# design.net
KiCad netlist of a schematic drawn in Altium Designer
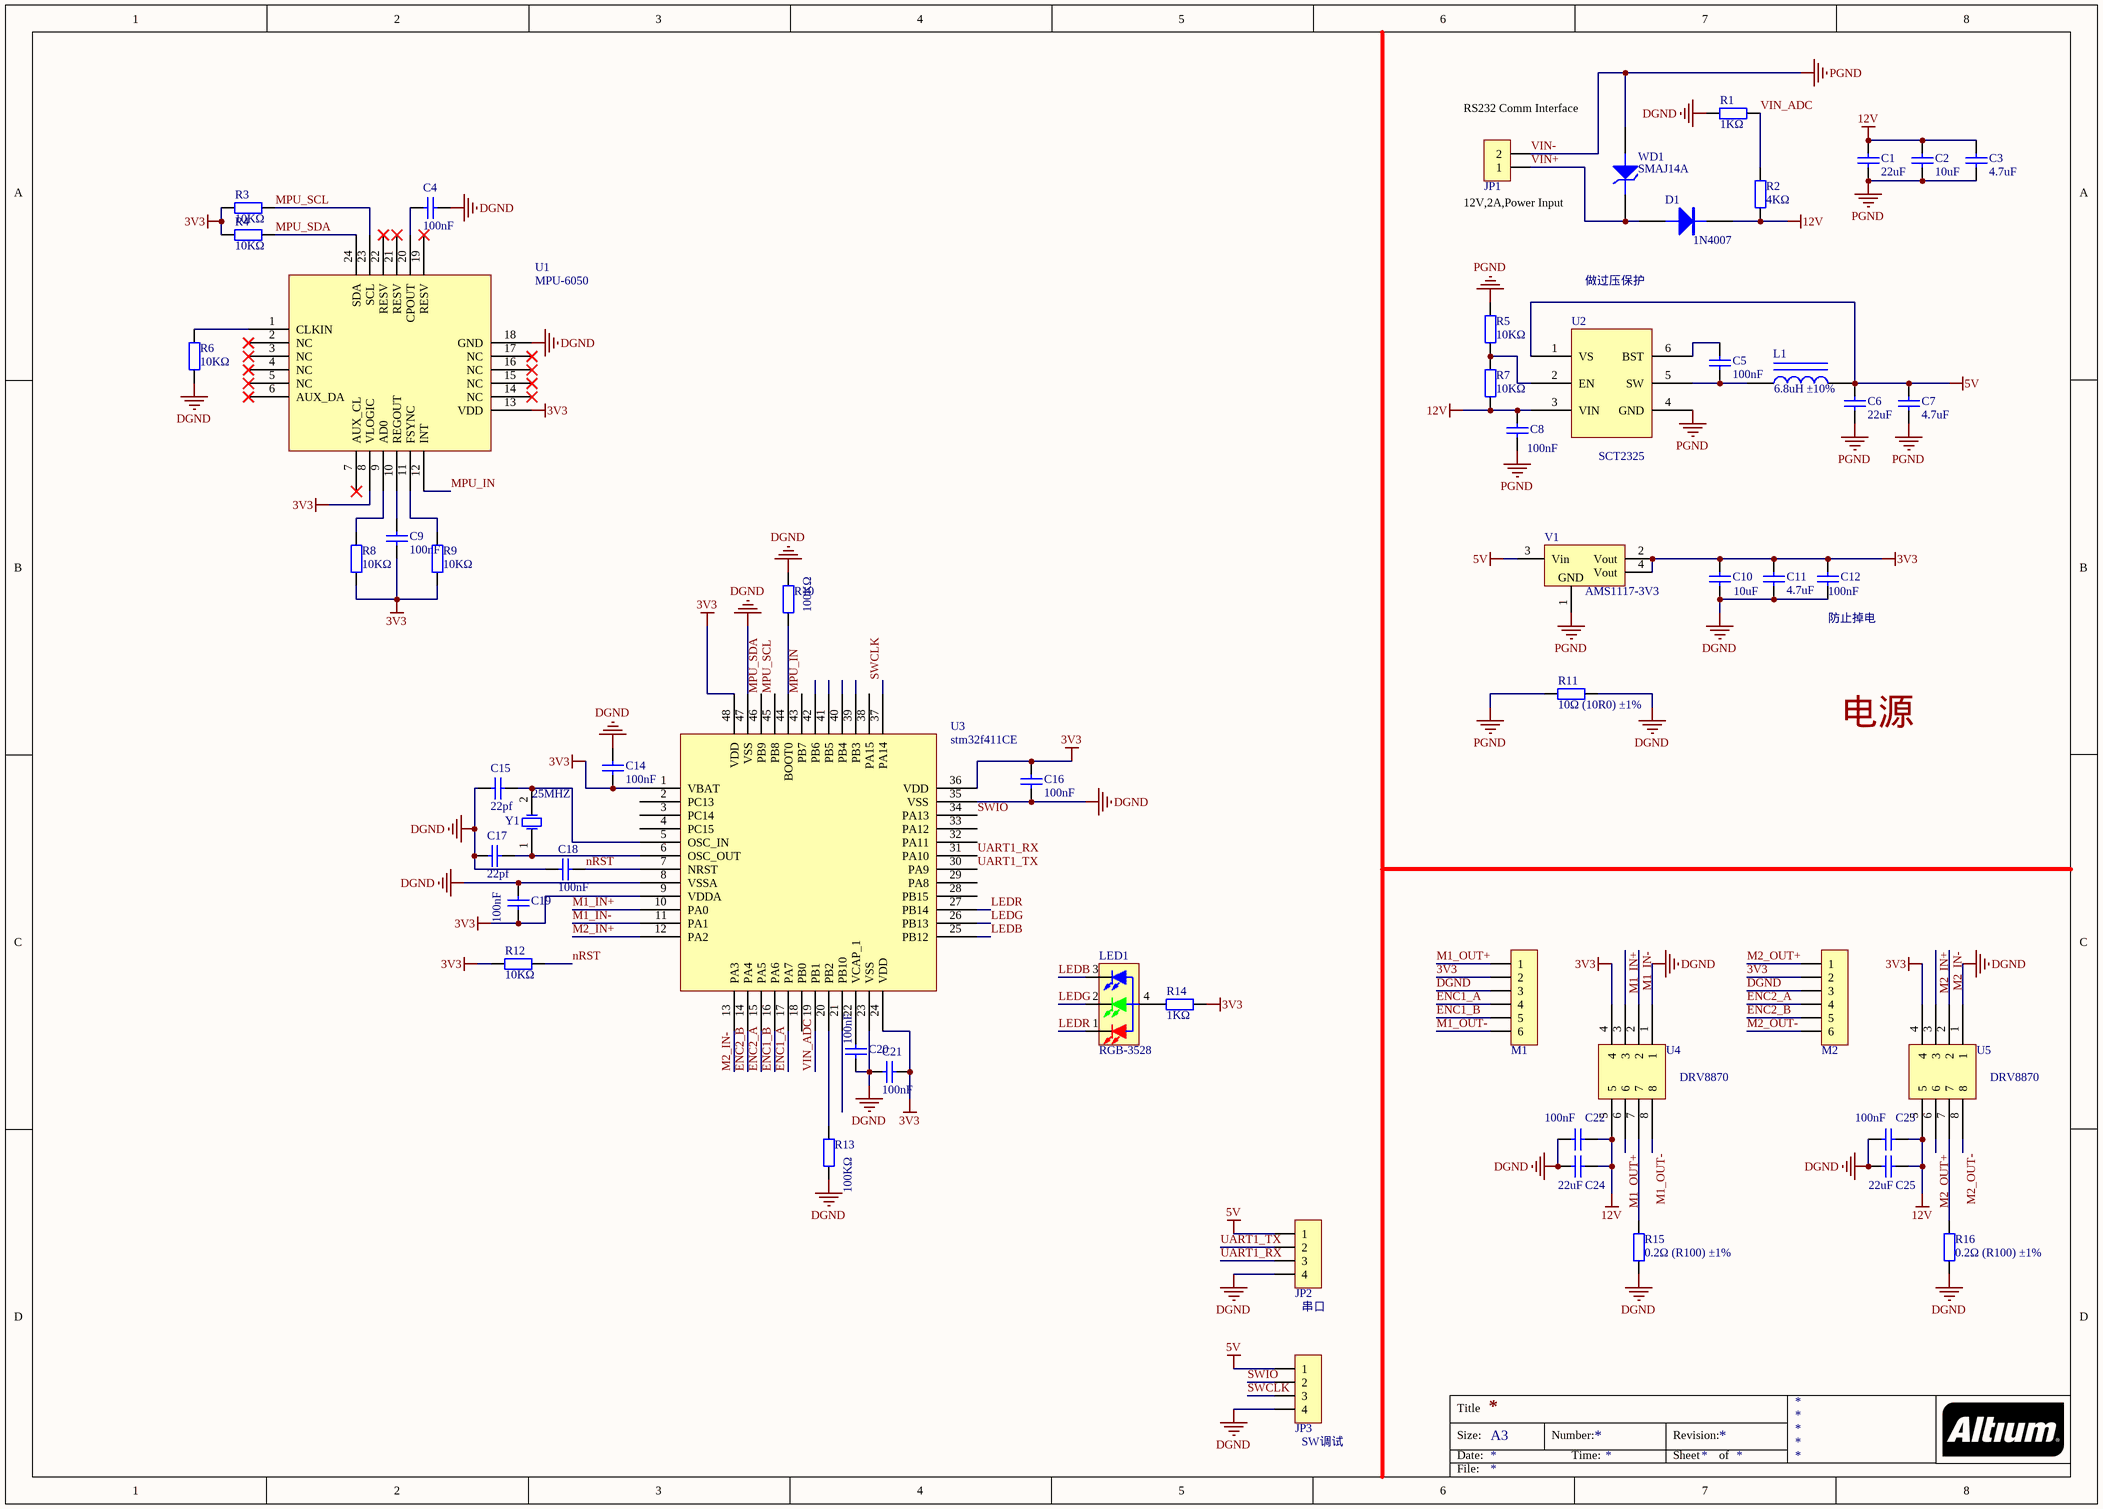
[diagram p0: 驱动控制板原理图.SchDoc]

(export (version "E")
  (design (tool "Eeschema 10.0.6"))
  (components
    (comp (ref "C1")
      (value "22uF")
      (footprint "LC-1206_C")
      (description "CAP TAN 22uF 20V T-Case B")
      (fields (field (name "PUBLISHER") "Altium Limited"))
      (libsource (lib "*") (part "Cap Semi"))
    )
    (comp (ref "C2")
      (value "10uF")
      (footprint "LC-0805_C")
      (description "CAP TAN 22uF 20V T-Case B")
      (fields (field (name "PUBLISHER") "Altium Limited"))
      (libsource (lib "*") (part "Cap Semi"))
    )
    (comp (ref "C3")
      (value "4.7uF")
      (footprint "LC-0603_C")
      (description "CAP TAN 22uF 20V T-Case B")
      (fields (field (name "PUBLISHER") "Altium Limited"))
      (libsource (lib "*") (part "Cap Semi"))
    )
    (comp (ref "C4")
      (value "100nF")
      (footprint "LC-0402_C")
      (description "CAP ceramic  0.1uF  X7R, SMD 0603")
      (fields
        (field (name "MANUFACTURER") "Generic Components")
        (field (name "PUBLISHER") "Altium Hobart Technology Centre")
      )
      (libsource (lib "*") (part "Cap"))
    )
    (comp (ref "C5")
      (value "100nF")
      (footprint "LC-0402_C")
      (description "贴片电容")
      (libsource (lib "立创封装库") (part "0603 100nF (104) 10% 50V"))
    )
    (comp (ref "C6")
      (value "22uF")
      (footprint "LC-1206_C")
      (description "贴片电容")
      (libsource (lib "立创封装库") (part "0805 22uF (226) 20% 25V"))
    )
    (comp (ref "C7")
      (value "4.7uF")
      (footprint "LC-0603_C")
      (description "CAP TAN 22uF 20V T-Case B")
      (fields (field (name "PUBLISHER") "Altium Limited"))
      (libsource (lib "*") (part "Cap Semi"))
    )
    (comp (ref "C8")
      (value "100nF")
      (footprint "LC-0402_C")
      (description "CAP ceramic  0.1uF  X7R, SMD 0603")
      (fields
        (field (name "MANUFACTURER") "Generic Components")
        (field (name "PUBLISHER") "Altium Hobart Technology Centre")
      )
      (libsource (lib "*") (part "Cap"))
    )
    (comp (ref "C9")
      (value "100nF")
      (footprint "LC-0402_C")
      (description "CAP ceramic  0.1uF  X7R, SMD 0603")
      (fields
        (field (name "MANUFACTURER") "Generic Components")
        (field (name "PUBLISHER") "Altium Hobart Technology Centre")
      )
      (libsource (lib "*") (part "Cap"))
    )
    (comp (ref "C10")
      (value "10uF")
      (footprint "LC-0805_C")
      (description "CAP TAN 22uF 20V T-Case B")
      (fields (field (name "PUBLISHER") "Altium Limited"))
      (libsource (lib "*") (part "Cap Semi"))
    )
    (comp (ref "C11")
      (value "4.7uF")
      (footprint "LC-0603_C")
      (description "CAP TAN 22uF 20V T-Case B")
      (fields (field (name "PUBLISHER") "Altium Limited"))
      (libsource (lib "*") (part "Cap Semi"))
    )
    (comp (ref "C12")
      (value "100nF")
      (footprint "LC-0402_C")
      (description "贴片电容")
      (libsource (lib "立创封装库") (part "0402 100nF (104) 10% 16V"))
    )
    (comp (ref "C14")
      (value "100nF")
      (footprint "LC-0402_C")
      (description "贴片电容")
      (libsource (lib "立创封装库") (part "0603 100nF (104) 10% 50V"))
    )
    (comp (ref "C15")
      (value "22pf")
      (footprint "LC-0402_C")
      (description "贴片电容")
      (libsource (lib "立创封装库") (part "0603 100nF (104) 10% 50V"))
    )
    (comp (ref "C16")
      (value "100nF")
      (footprint "LC-0402_C")
      (description "贴片电容")
      (libsource (lib "立创封装库") (part "0603 100nF (104) 10% 50V"))
    )
    (comp (ref "C17")
      (value "22pf")
      (footprint "LC-0402_C")
      (description "贴片电容")
      (libsource (lib "立创封装库") (part "0603 100nF (104) 10% 50V"))
    )
    (comp (ref "C18")
      (value "100nF")
      (footprint "LC-0402_C")
      (description "贴片电容")
      (libsource (lib "立创封装库") (part "0603 100nF (104) 10% 50V"))
    )
    (comp (ref "C19")
      (value "100nF")
      (footprint "LC-0402_C")
      (description "贴片电容")
      (libsource (lib "立创封装库") (part "0603 100nF (104) 10% 50V"))
    )
    (comp (ref "C20")
      (value "100nF")
      (footprint "LC-0402_C")
      (description "贴片电容")
      (libsource (lib "立创封装库") (part "0603 100nF (104) 10% 50V"))
    )
    (comp (ref "C21")
      (value "100nF")
      (footprint "LC-0402_C")
      (description "贴片电容")
      (libsource (lib "立创封装库") (part "0603 100nF (104) 10% 50V"))
    )
    (comp (ref "C22")
      (value "100nF")
      (footprint "LC-0805_C")
      (description "贴片电容")
      (libsource (lib "立创封装库") (part "0603 100nF (104) 10% 50V"))
    )
    (comp (ref "C23")
      (value "100nF")
      (footprint "LC-0805_C")
      (description "贴片电容")
      (libsource (lib "立创封装库") (part "0603 100nF (104) 10% 50V"))
    )
    (comp (ref "C24")
      (value "22uF")
      (footprint "LC-1206_C")
      (description "贴片电容")
      (libsource (lib "立创封装库") (part "0805 22uF (226) 20% 25V"))
    )
    (comp (ref "C25")
      (value "22uF")
      (footprint "LC-1206_C")
      (description "贴片电容")
      (libsource (lib "立创封装库") (part "0805 22uF (226) 20% 25V"))
    )
    (comp (ref "D1")
      (value "1N4007")
      (footprint "SMA")
      (description "Diode")
      (libsource (lib "*") (part "DIODE"))
    )
    (comp (ref "JP1")
      (value "HDR-1X2")
      (footprint "PH2.0-WI-2P")
      (description "2P接插件")
      (libsource (lib "5.3 - 接插件-脚距2.0") (part "Header 2"))
    )
    (comp (ref "JP2")
      (value "串口")
      (footprint "MX 1.25-WI-4P")
      (description "4P接插件")
      (libsource (lib "5.0 - 接插件-脚距1.25") (part "Header 4"))
    )
    (comp (ref "JP3")
      (value "SW调试")
      (footprint "MX 1.25-WI-4P")
      (description "4P接插件")
      (libsource (lib "5.0 - 接插件-脚距1.25") (part "Header 4"))
    )
    (comp (ref "L1")
      (value "6.8uH ±10%")
      (footprint "L-SMD-0630")
      (description "贴片电感")
      (libsource (lib "立创封装库") (part "1206 10uH 10%"))
    )
    (comp (ref "LED1")
      (value "RGB-3528")
      (footprint "LED 3528-4Pin")
      (description "3528三基色LED")
      (libsource (lib "0.3 - LED发光二极管") (part "LED-RGB 3528"))
    )
    (comp (ref "M1")
      (value "HDR-1X6")
      (footprint "ZH1.5-WI-6P")
      (description "6P接插件")
      (libsource (lib "5.2 - 接插件-脚距1.5") (part "Header 6"))
    )
    (comp (ref "M2")
      (value "HDR-1X6")
      (footprint "ZH1.5-WI-6P")
      (description "6P接插件")
      (libsource (lib "5.2 - 接插件-脚距1.5") (part "Header 6"))
    )
    (comp (ref "R1")
      (value "1KΩ")
      (footprint "LC-0402_R")
      (description "贴片电阻")
      (libsource (lib "") (part "0402 10KΩ (1002) 1%_1"))
    )
    (comp (ref "R2")
      (value "4KΩ")
      (footprint "LC-0402_R")
      (description "贴片电阻")
      (libsource (lib "立创封装库") (part "0402 10KΩ (1002) 1%"))
    )
    (comp (ref "R3")
      (value "10KΩ")
      (footprint "LC-0402_R")
      (description "贴片电阻")
      (libsource (lib "") (part "0402 10KΩ (1002) 1%_1"))
    )
    (comp (ref "R4")
      (value "10KΩ")
      (footprint "LC-0402_R")
      (description "贴片电阻")
      (libsource (lib "") (part "0402 10KΩ (1002) 1%_1"))
    )
    (comp (ref "R5")
      (value "10KΩ")
      (footprint "LC-0402_R")
      (description "贴片电阻")
      (libsource (lib "立创封装库") (part "0402 10KΩ (1002) 1%"))
    )
    (comp (ref "R6")
      (value "10KΩ")
      (footprint "LC-0402_R")
      (description "贴片电阻")
      (libsource (lib "立创封装库") (part "0402 10KΩ (1002) 1%"))
    )
    (comp (ref "R7")
      (value "10KΩ")
      (footprint "LC-0402_R")
      (description "贴片电阻")
      (libsource (lib "立创封装库") (part "0402 10KΩ (1002) 1%"))
    )
    (comp (ref "R8")
      (value "10KΩ")
      (footprint "LC-0402_R")
      (description "贴片电阻")
      (libsource (lib "立创封装库") (part "0402 10KΩ (1002) 1%"))
    )
    (comp (ref "R9")
      (value "10KΩ")
      (footprint "LC-0402_R")
      (description "贴片电阻")
      (libsource (lib "立创封装库") (part "0402 10KΩ (1002) 1%"))
    )
    (comp (ref "R10")
      (value "100KΩ")
      (footprint "LC-0402_R")
      (description "贴片电阻")
      (libsource (lib "立创封装库") (part "0603 110KΩ (1103) 1%"))
    )
    (comp (ref "R11")
      (value "10Ω (10R0) ±1%")
      (footprint "LC-1206_R")
      (description "贴片电阻")
      (libsource (lib "立创封装库") (part "1206 10Ω (10R0) 1%"))
    )
    (comp (ref "R12")
      (value "10KΩ")
      (footprint "LC-0402_R")
      (description "贴片电阻")
      (libsource (lib "") (part "0603 110KΩ (1103) 1%_1"))
    )
    (comp (ref "R13")
      (value "100KΩ")
      (footprint "LC-0402_R")
      (description "贴片电阻")
      (libsource (lib "立创封装库") (part "0603 110KΩ (1103) 1%"))
    )
    (comp (ref "R14")
      (value "1KΩ")
      (footprint "LC-0402_R")
      (description "贴片电阻")
      (libsource (lib "") (part "0603 110KΩ (1103) 1%_1"))
    )
    (comp (ref "R15")
      (value "0.2Ω (R100) ±1%")
      (footprint "LC-1206_R")
      (description "贴片电阻")
      (libsource (lib "立创封装库") (part "1206 0.1Ω (R100) 1%"))
    )
    (comp (ref "R16")
      (value "0.2Ω (R100) ±1%")
      (footprint "LC-1206_R")
      (description "贴片电阻")
      (libsource (lib "立创封装库") (part "1206 0.1Ω (R100) 1%"))
    )
    (comp (ref "U1")
      (value "MPU-6050")
      (footprint "QFN24 4x4_M")
      (description "传感器")
      (libsource (lib "立创封装库") (part "MPU-6050"))
    )
    (comp (ref "U2") (value "SCT2325") (footprint "SOT23-6") (libsource (lib "自建元器件库") (part "SCT2325")))
    (comp (ref "U3")
      (value "stm32f411CE")
      (footprint "QFN48 7X7_M")
      (libsource (lib "自建元器件库") (part "stm32f411"))
    )
    (comp (ref "U4") (value "DRV8870") (footprint "LC-SOP-8_150mil") (libsource (lib "*") (part "sop-8")))
    (comp (ref "U5") (value "DRV8870") (footprint "LC-SOP-8_150mil") (libsource (lib "*") (part "sop-8")))
    (comp (ref "V1")
      (value "AMS1117-3V3")
      (footprint "SOT223_L")
      (description "三端稳压芯片")
      (libsource (lib "1.1 - 电源类芯片") (part "AMS1117"))
    )
    (comp (ref "WD1")
      (value "SMAJ14A")
      (footprint "SMA")
      (description "Zener Diode")
      (libsource (lib "*") (part "ZENER3"))
    )
    (comp (ref "Y1")
      (value "25MHZ")
      (footprint "OSC 5032-2P")
      (description "QC6CB20.0000F18B23R，20MHZ")
      (fields (field (name "PUBLISHER") "Altium Limited"))
      (libsource (lib "*") (part "XTAL"))
    )
  )
  (nets
    (net (code "1") (name "/ENC1_A") (class "Default")
      (node (ref "M1") (pin "4") (pinfunction "4_4") (pintype "passive"))
      (node (ref "U3") (pin "17") (pinfunction "PA7_17") (pintype "passive"))
    )
    (net (code "2") (name "/ENC1_B") (class "Default")
      (node (ref "M1") (pin "5") (pinfunction "5_5") (pintype "passive"))
      (node (ref "U3") (pin "16") (pinfunction "PA6_16") (pintype "passive"))
    )
    (net (code "3") (name "/ENC2_A") (class "Default")
      (node (ref "M2") (pin "4") (pinfunction "4_4") (pintype "passive"))
      (node (ref "U3") (pin "15") (pinfunction "PA5_15") (pintype "passive"))
    )
    (net (code "4") (name "/ENC2_B") (class "Default")
      (node (ref "M2") (pin "5") (pinfunction "5_5") (pintype "passive"))
      (node (ref "U3") (pin "14") (pinfunction "PA4_14") (pintype "passive"))
    )
    (net (code "5") (name "/LEDB") (class "Default")
      (node (ref "LED1") (pin "3") (pinfunction "BULE_K_3") (pintype "passive"))
      (node (ref "U3") (pin "25") (pinfunction "PB12_25") (pintype "passive"))
    )
    (net (code "6") (name "/LEDG") (class "Default")
      (node (ref "LED1") (pin "2") (pinfunction "GREEN_K_2") (pintype "passive"))
      (node (ref "U3") (pin "26") (pinfunction "PB13_26") (pintype "passive"))
    )
    (net (code "7") (name "/LEDR") (class "Default")
      (node (ref "LED1") (pin "1") (pinfunction "RED_K_1") (pintype "passive"))
      (node (ref "U3") (pin "27") (pinfunction "PB14_27") (pintype "passive"))
    )
    (net (code "8") (name "/M1_IN+") (class "Default")
      (node (ref "U3") (pin "10") (pinfunction "PA0_10") (pintype "passive"))
      (node (ref "U4") (pin "3") (pinfunction "3_3") (pintype "passive"))
    )
    (net (code "9") (name "/M1_IN-") (class "Default")
      (node (ref "U3") (pin "11") (pinfunction "PA1_11") (pintype "passive"))
      (node (ref "U4") (pin "2") (pinfunction "2_2") (pintype "passive"))
    )
    (net (code "10") (name "/M1_OUT+") (class "Default")
      (node (ref "M1") (pin "1") (pinfunction "1_1") (pintype "passive"))
      (node (ref "U4") (pin "6") (pinfunction "6_6") (pintype "passive"))
    )
    (net (code "11") (name "/M1_OUT-") (class "Default")
      (node (ref "M1") (pin "6") (pinfunction "6_6") (pintype "passive"))
      (node (ref "U4") (pin "8") (pinfunction "8_8") (pintype "passive"))
    )
    (net (code "12") (name "/M2_IN+") (class "Default")
      (node (ref "U3") (pin "12") (pinfunction "PA2_12") (pintype "passive"))
      (node (ref "U5") (pin "3") (pinfunction "3_3") (pintype "passive"))
    )
    (net (code "13") (name "/M2_IN-") (class "Default")
      (node (ref "U3") (pin "13") (pinfunction "PA3_13") (pintype "passive"))
      (node (ref "U5") (pin "2") (pinfunction "2_2") (pintype "passive"))
    )
    (net (code "14") (name "/M2_OUT+") (class "Default")
      (node (ref "M2") (pin "1") (pinfunction "1_1") (pintype "passive"))
      (node (ref "U5") (pin "6") (pinfunction "6_6") (pintype "passive"))
    )
    (net (code "15") (name "/M2_OUT-") (class "Default")
      (node (ref "M2") (pin "6") (pinfunction "6_6") (pintype "passive"))
      (node (ref "U5") (pin "8") (pinfunction "8_8") (pintype "passive"))
    )
    (net (code "16") (name "/MPU_IN") (class "Default")
      (node (ref "U1") (pin "12") (pinfunction "INT_12") (pintype "passive"))
      (node (ref "U3") (pin "43") (pinfunction "PB7_43") (pintype "passive"))
    )
    (net (code "17") (name "/MPU_SCL") (class "Default")
      (node (ref "R3") (pin "1") (pinfunction "1_1") (pintype "passive"))
      (node (ref "U1") (pin "23") (pinfunction "SCL_23") (pintype "passive"))
      (node (ref "U3") (pin "45") (pinfunction "PB8_45") (pintype "passive"))
    )
    (net (code "18") (name "/MPU_SDA") (class "Default")
      (node (ref "R4") (pin "1") (pinfunction "1_1") (pintype "passive"))
      (node (ref "U1") (pin "24") (pinfunction "SDA_24") (pintype "passive"))
      (node (ref "U3") (pin "46") (pinfunction "PB9_46") (pintype "passive"))
    )
    (net (code "19") (name "/SWCLK") (class "Default")
      (node (ref "JP3") (pin "3") (pinfunction "3_3") (pintype "passive"))
      (node (ref "U3") (pin "37") (pinfunction "PA14_37") (pintype "passive"))
    )
    (net (code "20") (name "/SWIO") (class "Default")
      (node (ref "JP3") (pin "2") (pinfunction "2_2") (pintype "passive"))
      (node (ref "U3") (pin "34") (pinfunction "PA13_34") (pintype "passive"))
    )
    (net (code "21") (name "/UART1_RX") (class "Default")
      (node (ref "JP2") (pin "3") (pinfunction "3_3") (pintype "passive"))
      (node (ref "U3") (pin "31") (pinfunction "PA10_31") (pintype "passive"))
    )
    (net (code "22") (name "/UART1_TX") (class "Default")
      (node (ref "JP2") (pin "2") (pinfunction "2_2") (pintype "passive"))
      (node (ref "U3") (pin "30") (pinfunction "PA9_30") (pintype "passive"))
    )
    (net (code "23") (name "/VIN+") (class "Default")
      (node (ref "D1") (pin "1") (pinfunction "A_1") (pintype "passive"))
      (node (ref "JP1") (pin "1") (pinfunction "1_1") (pintype "passive"))
      (node (ref "WD1") (pin "2") (pinfunction "K_2") (pintype "passive"))
    )
    (net (code "24") (name "/VIN_ADC") (class "Default")
      (node (ref "R1") (pin "1") (pinfunction "1_1") (pintype "passive"))
      (node (ref "R2") (pin "2") (pinfunction "2_2") (pintype "passive"))
      (node (ref "U3") (pin "19") (pinfunction "PB1_19") (pintype "passive"))
    )
    (net (code "25") (name "/nRST") (class "Default")
      (node (ref "C18") (pin "2") (pinfunction "2_2") (pintype "passive"))
      (node (ref "R12") (pin "2") (pinfunction "2_2") (pintype "passive"))
      (node (ref "U3") (pin "7") (pinfunction "NRST_7") (pintype "passive"))
    )
    (net (code "26") (name "3V3") (class "Default")
      (node (ref "C10") (pin "1") (pinfunction "1_1") (pintype "passive"))
      (node (ref "C11") (pin "1") (pinfunction "1_1") (pintype "passive"))
      (node (ref "C12") (pin "2") (pinfunction "2_2") (pintype "passive"))
      (node (ref "C14") (pin "2") (pinfunction "2_2") (pintype "passive"))
      (node (ref "C16") (pin "2") (pinfunction "2_2") (pintype "passive"))
      (node (ref "C19") (pin "1") (pinfunction "1_1") (pintype "passive"))
      (node (ref "C21") (pin "1") (pinfunction "1_1") (pintype "passive"))
      (node (ref "C9") (pin "2") (pinfunction "2_2") (pintype "passive"))
      (node (ref "M1") (pin "2") (pinfunction "2_2") (pintype "passive"))
      (node (ref "M2") (pin "2") (pinfunction "2_2") (pintype "passive"))
      (node (ref "R12") (pin "1") (pinfunction "1_1") (pintype "passive"))
      (node (ref "R14") (pin "2") (pinfunction "2_2") (pintype "passive"))
      (node (ref "R3") (pin "2") (pinfunction "2_2") (pintype "passive"))
      (node (ref "R4") (pin "2") (pinfunction "2_2") (pintype "passive"))
      (node (ref "R8") (pin "1") (pinfunction "1_1") (pintype "passive"))
      (node (ref "R9") (pin "1") (pinfunction "1_1") (pintype "passive"))
      (node (ref "U1") (pin "13") (pinfunction "VDD_13") (pintype "passive"))
      (node (ref "U1") (pin "8") (pinfunction "VLOGIC_8") (pintype "passive"))
      (node (ref "U3") (pin "1") (pinfunction "VBAT_1") (pintype "passive"))
      (node (ref "U3") (pin "24") (pinfunction "VDD_24") (pintype "passive"))
      (node (ref "U3") (pin "36") (pinfunction "VDD_36") (pintype "passive"))
      (node (ref "U3") (pin "48") (pinfunction "VDD_48") (pintype "passive"))
      (node (ref "U3") (pin "9") (pinfunction "VDDA_9") (pintype "passive"))
      (node (ref "U4") (pin "4") (pinfunction "4_4") (pintype "passive"))
      (node (ref "U5") (pin "4") (pinfunction "4_4") (pintype "passive"))
      (node (ref "V1") (pin "2") (pinfunction "Vout_2") (pintype "passive"))
      (node (ref "V1") (pin "4") (pinfunction "Vout_4") (pintype "passive"))
    )
    (net (code "27") (name "5V") (class "Default")
      (node (ref "C6") (pin "2") (pinfunction "2_2") (pintype "passive"))
      (node (ref "C7") (pin "1") (pinfunction "1_1") (pintype "passive"))
      (node (ref "JP2") (pin "1") (pinfunction "1_1") (pintype "passive"))
      (node (ref "JP3") (pin "1") (pinfunction "1_1") (pintype "passive"))
      (node (ref "L1") (pin "2") (pinfunction "2_2") (pintype "passive"))
      (node (ref "U2") (pin "1") (pinfunction "VS_1") (pintype "passive"))
      (node (ref "V1") (pin "3") (pinfunction "Vin_3") (pintype "passive"))
    )
    (net (code "28") (name "12V") (class "Default")
      (node (ref "C1") (pin "1") (pinfunction "1_1") (pintype "passive"))
      (node (ref "C2") (pin "1") (pinfunction "1_1") (pintype "passive"))
      (node (ref "C22") (pin "1") (pinfunction "1_1") (pintype "passive"))
      (node (ref "C23") (pin "1") (pinfunction "1_1") (pintype "passive"))
      (node (ref "C24") (pin "1") (pinfunction "1_1") (pintype "passive"))
      (node (ref "C25") (pin "1") (pinfunction "1_1") (pintype "passive"))
      (node (ref "C3") (pin "1") (pinfunction "1_1") (pintype "passive"))
      (node (ref "C8") (pin "2") (pinfunction "2_2") (pintype "passive"))
      (node (ref "D1") (pin "2") (pinfunction "K_2") (pintype "passive"))
      (node (ref "R2") (pin "1") (pinfunction "1_1") (pintype "passive"))
      (node (ref "R7") (pin "1") (pinfunction "1_1") (pintype "passive"))
      (node (ref "U2") (pin "3") (pinfunction "VIN_3") (pintype "passive"))
      (node (ref "U4") (pin "5") (pinfunction "5_5") (pintype "passive"))
      (node (ref "U5") (pin "5") (pinfunction "5_5") (pintype "passive"))
    )
    (net (code "29") (name "DGND") (class "Default")
      (node (ref "C10") (pin "2") (pinfunction "2_2") (pintype "passive"))
      (node (ref "C11") (pin "2") (pinfunction "2_2") (pintype "passive"))
      (node (ref "C12") (pin "1") (pinfunction "1_1") (pintype "passive"))
      (node (ref "C14") (pin "1") (pinfunction "1_1") (pintype "passive"))
      (node (ref "C15") (pin "1") (pinfunction "1_1") (pintype "passive"))
      (node (ref "C16") (pin "1") (pinfunction "1_1") (pintype "passive"))
      (node (ref "C17") (pin "1") (pinfunction "1_1") (pintype "passive"))
      (node (ref "C18") (pin "1") (pinfunction "1_1") (pintype "passive"))
      (node (ref "C19") (pin "2") (pinfunction "2_2") (pintype "passive"))
      (node (ref "C20") (pin "1") (pinfunction "1_1") (pintype "passive"))
      (node (ref "C21") (pin "2") (pinfunction "2_2") (pintype "passive"))
      (node (ref "C22") (pin "2") (pinfunction "2_2") (pintype "passive"))
      (node (ref "C23") (pin "2") (pinfunction "2_2") (pintype "passive"))
      (node (ref "C24") (pin "2") (pinfunction "2_2") (pintype "passive"))
      (node (ref "C25") (pin "2") (pinfunction "2_2") (pintype "passive"))
      (node (ref "C4") (pin "2") (pinfunction "2_2") (pintype "passive"))
      (node (ref "JP2") (pin "4") (pinfunction "4_4") (pintype "passive"))
      (node (ref "JP3") (pin "4") (pinfunction "4_4") (pintype "passive"))
      (node (ref "M1") (pin "3") (pinfunction "3_3") (pintype "passive"))
      (node (ref "M2") (pin "3") (pinfunction "3_3") (pintype "passive"))
      (node (ref "R1") (pin "2") (pinfunction "2_2") (pintype "passive"))
      (node (ref "R10") (pin "2") (pinfunction "2_2") (pintype "passive"))
      (node (ref "R11") (pin "2") (pinfunction "2_2") (pintype "passive"))
      (node (ref "R13") (pin "1") (pinfunction "1_1") (pintype "passive"))
      (node (ref "R15") (pin "2") (pinfunction "2_2") (pintype "passive"))
      (node (ref "R16") (pin "2") (pinfunction "2_2") (pintype "passive"))
      (node (ref "R6") (pin "1") (pinfunction "1_1") (pintype "passive"))
      (node (ref "U1") (pin "18") (pinfunction "GND_18") (pintype "passive"))
      (node (ref "U3") (pin "23") (pinfunction "VSS_23") (pintype "passive"))
      (node (ref "U3") (pin "35") (pinfunction "VSS_35") (pintype "passive"))
      (node (ref "U3") (pin "47") (pinfunction "VSS_47") (pintype "passive"))
      (node (ref "U3") (pin "8") (pinfunction "VSSA_8") (pintype "passive"))
      (node (ref "U4") (pin "1") (pinfunction "1_1") (pintype "passive"))
      (node (ref "U5") (pin "1") (pinfunction "1_1") (pintype "passive"))
    )
    (net (code "30") (name "Net-(LED1-A)") (class "Default")
      (node (ref "LED1") (pin "4") (pinfunction "A_4") (pintype "passive"))
      (node (ref "R14") (pin "1") (pinfunction "1_1") (pintype "passive"))
    )
    (net (code "31") (name "Net-(R15-Pad1)") (class "Default")
      (node (ref "R15") (pin "1") (pinfunction "1_1") (pintype "passive"))
      (node (ref "U4") (pin "7") (pinfunction "7_7") (pintype "passive"))
    )
    (net (code "32") (name "Net-(R16-Pad1)") (class "Default")
      (node (ref "R16") (pin "1") (pinfunction "1_1") (pintype "passive"))
      (node (ref "U5") (pin "7") (pinfunction "7_7") (pintype "passive"))
    )
    (net (code "33") (name "Net-(U1-AD0)") (class "Default")
      (node (ref "R8") (pin "2") (pinfunction "2_2") (pintype "passive"))
      (node (ref "U1") (pin "9") (pinfunction "AD0_9") (pintype "passive"))
    )
    (net (code "34") (name "Net-(U1-CLKIN)") (class "Default")
      (node (ref "R6") (pin "2") (pinfunction "2_2") (pintype "passive"))
      (node (ref "U1") (pin "1") (pinfunction "CLKIN_1") (pintype "passive"))
    )
    (net (code "35") (name "Net-(U1-CPOUT)") (class "Default")
      (node (ref "C4") (pin "1") (pinfunction "1_1") (pintype "passive"))
      (node (ref "U1") (pin "20") (pinfunction "CPOUT_20") (pintype "passive"))
    )
    (net (code "36") (name "Net-(U1-FSYNC)") (class "Default")
      (node (ref "R9") (pin "2") (pinfunction "2_2") (pintype "passive"))
      (node (ref "U1") (pin "11") (pinfunction "FSYNC_11") (pintype "passive"))
    )
    (net (code "37") (name "Net-(U1-REGOUT)") (class "Default")
      (node (ref "C9") (pin "1") (pinfunction "1_1") (pintype "passive"))
      (node (ref "U1") (pin "10") (pinfunction "REGOUT_10") (pintype "passive"))
    )
    (net (code "38") (name "Net-(U2-BST)") (class "Default")
      (node (ref "C5") (pin "2") (pinfunction "2_2") (pintype "passive"))
      (node (ref "U2") (pin "6") (pinfunction "BST_6") (pintype "passive"))
    )
    (net (code "39") (name "Net-(U2-EN)") (class "Default")
      (node (ref "R5") (pin "1") (pinfunction "1_1") (pintype "passive"))
      (node (ref "R7") (pin "2") (pinfunction "2_2") (pintype "passive"))
      (node (ref "U2") (pin "2") (pinfunction "EN_2") (pintype "passive"))
    )
    (net (code "40") (name "Net-(U2-SW)") (class "Default")
      (node (ref "C5") (pin "1") (pinfunction "1_1") (pintype "passive"))
      (node (ref "L1") (pin "1") (pinfunction "1_1") (pintype "passive"))
      (node (ref "U2") (pin "5") (pinfunction "SW_5") (pintype "passive"))
    )
    (net (code "41") (name "Net-(U3-BOOT0)") (class "Default")
      (node (ref "R10") (pin "1") (pinfunction "1_1") (pintype "passive"))
      (node (ref "U3") (pin "44") (pinfunction "BOOT0_44") (pintype "passive"))
    )
    (net (code "42") (name "Net-(U3-OSC_IN)") (class "Default")
      (node (ref "C15") (pin "2") (pinfunction "2_2") (pintype "passive"))
      (node (ref "U3") (pin "5") (pinfunction "OSC_IN_5") (pintype "passive"))
      (node (ref "Y1") (pin "2") (pinfunction "OSC2_2") (pintype "passive"))
    )
    (net (code "43") (name "Net-(U3-OSC_OUT)") (class "Default")
      (node (ref "C17") (pin "2") (pinfunction "2_2") (pintype "passive"))
      (node (ref "U3") (pin "6") (pinfunction "OSC_OUT_6") (pintype "passive"))
      (node (ref "Y1") (pin "1") (pinfunction "OSC1_1") (pintype "passive"))
    )
    (net (code "44") (name "Net-(U3-PB2)") (class "Default")
      (node (ref "R13") (pin "2") (pinfunction "2_2") (pintype "passive"))
      (node (ref "U3") (pin "20") (pinfunction "PB2_20") (pintype "passive"))
    )
    (net (code "45") (name "Net-(U3-VCAP_1)") (class "Default")
      (node (ref "C20") (pin "2") (pinfunction "2_2") (pintype "passive"))
      (node (ref "U3") (pin "22") (pinfunction "VCAP_1_22") (pintype "passive"))
    )
    (net (code "46") (name "PGND") (class "Default")
      (node (ref "C1") (pin "2") (pinfunction "2_2") (pintype "passive"))
      (node (ref "C2") (pin "2") (pinfunction "2_2") (pintype "passive"))
      (node (ref "C3") (pin "2") (pinfunction "2_2") (pintype "passive"))
      (node (ref "C6") (pin "1") (pinfunction "1_1") (pintype "passive"))
      (node (ref "C7") (pin "2") (pinfunction "2_2") (pintype "passive"))
      (node (ref "C8") (pin "1") (pinfunction "1_1") (pintype "passive"))
      (node (ref "JP1") (pin "2") (pinfunction "2_2") (pintype "passive"))
      (node (ref "R11") (pin "1") (pinfunction "1_1") (pintype "passive"))
      (node (ref "R5") (pin "2") (pinfunction "2_2") (pintype "passive"))
      (node (ref "U2") (pin "4") (pinfunction "GND_4") (pintype "passive"))
      (node (ref "V1") (pin "1") (pinfunction "GND_1") (pintype "passive"))
      (node (ref "WD1") (pin "1") (pinfunction "A_1") (pintype "passive"))
    )
    (net (code "47") (name "unconnected-(U1-AUX_CL-Pad7)") (class "Default")
      (node (ref "U1") (pin "7") (pinfunction "AUX_CL_7") (pintype "passive+no_connect"))
    )
    (net (code "48") (name "unconnected-(U1-AUX_DA-Pad6)") (class "Default")
      (node (ref "U1") (pin "6") (pinfunction "AUX_DA_6") (pintype "passive+no_connect"))
    )
    (net (code "49") (name "unconnected-(U1-NC-Pad2)") (class "Default")
      (node (ref "U1") (pin "2") (pinfunction "NC_2") (pintype "passive+no_connect"))
    )
    (net (code "50") (name "unconnected-(U1-NC-Pad3)") (class "Default")
      (node (ref "U1") (pin "3") (pinfunction "NC_3") (pintype "passive+no_connect"))
    )
    (net (code "51") (name "unconnected-(U1-NC-Pad4)") (class "Default")
      (node (ref "U1") (pin "4") (pinfunction "NC_4") (pintype "passive+no_connect"))
    )
    (net (code "52") (name "unconnected-(U1-NC-Pad5)") (class "Default")
      (node (ref "U1") (pin "5") (pinfunction "NC_5") (pintype "passive+no_connect"))
    )
    (net (code "53") (name "unconnected-(U1-NC-Pad14)") (class "Default")
      (node (ref "U1") (pin "14") (pinfunction "NC_14") (pintype "passive+no_connect"))
    )
    (net (code "54") (name "unconnected-(U1-NC-Pad15)") (class "Default")
      (node (ref "U1") (pin "15") (pinfunction "NC_15") (pintype "passive+no_connect"))
    )
    (net (code "55") (name "unconnected-(U1-NC-Pad16)") (class "Default")
      (node (ref "U1") (pin "16") (pinfunction "NC_16") (pintype "passive+no_connect"))
    )
    (net (code "56") (name "unconnected-(U1-NC-Pad17)") (class "Default")
      (node (ref "U1") (pin "17") (pinfunction "NC_17") (pintype "passive+no_connect"))
    )
    (net (code "57") (name "unconnected-(U1-RESV-Pad19)") (class "Default")
      (node (ref "U1") (pin "19") (pinfunction "RESV_19") (pintype "passive+no_connect"))
    )
    (net (code "58") (name "unconnected-(U1-RESV-Pad21)") (class "Default")
      (node (ref "U1") (pin "21") (pinfunction "RESV_21") (pintype "passive+no_connect"))
    )
    (net (code "59") (name "unconnected-(U1-RESV-Pad22)") (class "Default")
      (node (ref "U1") (pin "22") (pinfunction "RESV_22") (pintype "passive+no_connect"))
    )
    (net (code "60") (name "unconnected-(U3-PA8-Pad29)") (class "Default")
      (node (ref "U3") (pin "29") (pinfunction "PA8_29") (pintype "passive"))
    )
    (net (code "61") (name "unconnected-(U3-PA11-Pad32)") (class "Default")
      (node (ref "U3") (pin "32") (pinfunction "PA11_32") (pintype "passive"))
    )
    (net (code "62") (name "unconnected-(U3-PA12-Pad33)") (class "Default")
      (node (ref "U3") (pin "33") (pinfunction "PA12_33") (pintype "passive"))
    )
    (net (code "63") (name "unconnected-(U3-PA15-Pad38)") (class "Default")
      (node (ref "U3") (pin "38") (pinfunction "PA15_38") (pintype "passive"))
    )
    (net (code "64") (name "unconnected-(U3-PB0-Pad18)") (class "Default")
      (node (ref "U3") (pin "18") (pinfunction "PB0_18") (pintype "passive"))
    )
    (net (code "65") (name "unconnected-(U3-PB3-Pad39)") (class "Default")
      (node (ref "U3") (pin "39") (pinfunction "PB3_39") (pintype "passive"))
    )
    (net (code "66") (name "unconnected-(U3-PB4-Pad40)") (class "Default")
      (node (ref "U3") (pin "40") (pinfunction "PB4_40") (pintype "passive"))
    )
    (net (code "67") (name "unconnected-(U3-PB5-Pad41)") (class "Default")
      (node (ref "U3") (pin "41") (pinfunction "PB5_41") (pintype "passive"))
    )
    (net (code "68") (name "unconnected-(U3-PB6-Pad42)") (class "Default")
      (node (ref "U3") (pin "42") (pinfunction "PB6_42") (pintype "passive"))
    )
    (net (code "69") (name "unconnected-(U3-PB10-Pad21)") (class "Default")
      (node (ref "U3") (pin "21") (pinfunction "PB10_21") (pintype "passive"))
    )
    (net (code "70") (name "unconnected-(U3-PB15-Pad28)") (class "Default")
      (node (ref "U3") (pin "28") (pinfunction "PB15_28") (pintype "passive"))
    )
    (net (code "71") (name "unconnected-(U3-PC13-Pad2)") (class "Default")
      (node (ref "U3") (pin "2") (pinfunction "PC13_2") (pintype "passive"))
    )
    (net (code "72") (name "unconnected-(U3-PC14-Pad3)") (class "Default")
      (node (ref "U3") (pin "3") (pinfunction "PC14_3") (pintype "passive"))
    )
    (net (code "73") (name "unconnected-(U3-PC15-Pad4)") (class "Default")
      (node (ref "U3") (pin "4") (pinfunction "PC15_4") (pintype "passive"))
    )
  )
)
